# pmu.net
KiCad netlist of a schematic drawn in Altium Designer
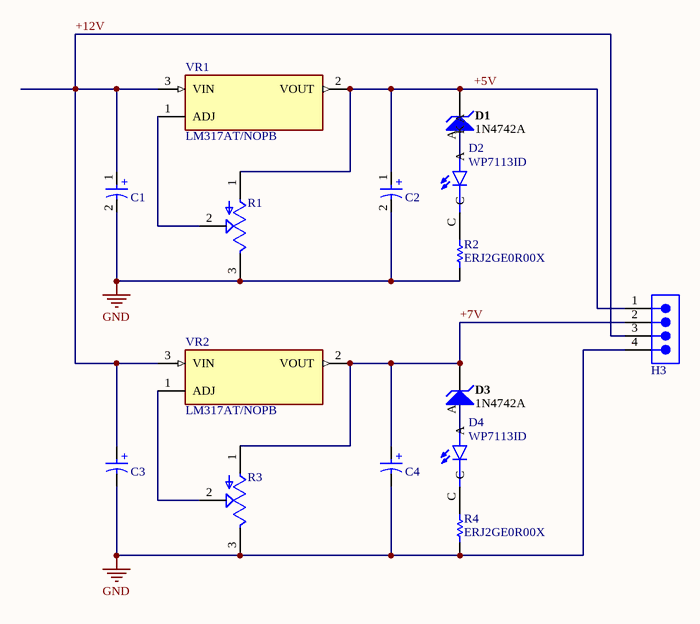
[diagram p0: pmu.SchDoc]

(export (version "E")
  (design (tool "Eeschema 10.0.6"))
  (components
    (comp (ref "C1")
      (value "2.2µF")
      (footprint "pmu:WCAP-ATG5_D5H11")
      (description "WCAP-ATG5 Aluminum Electrolytic Capacitor, Radial, THT, D5 x H11mm, 2.2µF, 50V")
      (fields
        (field (name "MANUFACTURER PART NUMBER") "860020672006")
        (field (name "MANUFACTURER") "Wurth Elektronik")
      )
      (libsource (lib "1ufcap-Altium_WCAP-ATG5_rev22d") (part "860020672006"))
    )
    (comp (ref "C2")
      (value "1.1uF")
      (footprint "pmu:WCAP-ATG5_D5H11")
      (description "WCAP-ATG5 Aluminum Electrolytic Capacitor, Radial, THT, D5 x H11mm, 2.2µF, 50V")
      (fields
        (field (name "MANUFACTURER PART NUMBER") "860020672006")
        (field (name "MANUFACTURER") "Wurth Elektronik")
      )
      (libsource (lib "1ufcap-Altium_WCAP-ATG5_rev22d") (part "860020672006"))
    )
    (comp (ref "C3")
      (value "2.2µF")
      (footprint "pmu:WCAP-ATG5_D5H11")
      (description "WCAP-ATG5 Aluminum Electrolytic Capacitor, Radial, THT, D5 x H11mm, 2.2µF, 50V")
      (fields
        (field (name "MANUFACTURER PART NUMBER") "860020672006")
        (field (name "MANUFACTURER") "Wurth Elektronik")
      )
      (libsource (lib "") (part "860020672006_1"))
    )
    (comp (ref "C4")
      (value "1.1uF")
      (footprint "pmu:WCAP-ATG5_D5H11")
      (description "WCAP-ATG5 Aluminum Electrolytic Capacitor, Radial, THT, D5 x H11mm, 2.2µF, 50V")
      (fields
        (field (name "MANUFACTURER PART NUMBER") "860020672006")
        (field (name "MANUFACTURER") "Wurth Elektronik")
      )
      (libsource (lib "") (part "860020672006_1"))
    )
    (comp (ref "D1")
      (value "1N4742A")
      (footprint "FAIR-DO-41-2_V")
      (description "Zener Diode, 12V, 1W, 5%, -65 to 200 degC, 2-Pin DO-41, Body 2.72 x 5.2 mm, RoHS")
      (fields (field (name "TOLERANCE") "5%") (field (name "MANUFACTURER") "Fairchild Semiconductor"))
      (libsource (lib "Altium Content Vault") (part "FAIR-DZEN-A1K2-2"))
    )
    (comp (ref "D2")
      (value "WP7113ID")
      (footprint "pmu:LED_WP7113ID")
      (description "Red 617nm LED Indication - Discrete 2V Radial")
      (fields (field (name "MF") "Kingbright"))
      (libsource (lib "leds-WP7113ID") (part "WP7113ID"))
    )
    (comp (ref "D3")
      (value "1N4742A")
      (footprint "FAIR-DO-41-2_V")
      (description "Zener Diode, 12V, 1W, 5%, -65 to 200 degC, 2-Pin DO-41, Body 2.72 x 5.2 mm, RoHS")
      (fields (field (name "TOLERANCE") "5%") (field (name "MANUFACTURER") "Fairchild Semiconductor"))
      (libsource (lib "") (part "FAIR-DZEN-A1K2-2_1"))
    )
    (comp (ref "D4")
      (value "WP7113ID")
      (footprint "pmu:LED_WP7113ID")
      (description "Red 617nm LED Indication - Discrete 2V Radial")
      (fields (field (name "MF") "Kingbright"))
      (libsource (lib "leds-WP7113ID") (part "WP7113ID"))
    )
    (comp (ref "H3")
      (value "61300411121")
      (footprint "61300411121")
      (description "WR-PHD Pin Header, THT, Vertical, pitch 2.54mm, 1 Row, 4P")
      (fields (field (name "MANUFACTURER") "Wurth Elektronik"))
      (libsource (lib "pmu") (part "61300411121"))
    )
    (comp (ref "R1")
      (value "~")
      (footprint "TRIM_3362P-1-103LF")
      (description "10 kOhms 0.5W, 1/2W PC Pins Through Hole Trimmer Potentiometer Cermet 1 Turn Top Adjustment")
      (fields (field (name "DIGI-KEY_PART_NUMBER") "3362P-103LF-ND") (field (name "MF") "Bourns"))
      (libsource (lib "*") (part "3362P-1-103LF"))
    )
    (comp (ref "R2")
      (value "ERJ2GE0R00X")
      (footprint "RESC1005X40X25LL05T05")
      (description "Chip Resistor, 0 Ohm, 0.1 W, -55 to 155 degC, 0402 (1005 Metric), RoHS, Tape and Reel")
      (fields (field (name "MANUFACTURER") "Panasonic") (field (name "TOLERANCE") "5%"))
      (libsource (lib "Altium Content Vault") (part "RES-2"))
    )
    (comp (ref "R3")
      (value "~")
      (footprint "TRIM_3362P-1-103LF")
      (description "10 kOhms 0.5W, 1/2W PC Pins Through Hole Trimmer Potentiometer Cermet 1 Turn Top Adjustment")
      (fields (field (name "DIGI-KEY_PART_NUMBER") "3362P-103LF-ND") (field (name "MF") "Bourns"))
      (libsource (lib "*") (part "3362P-1-103LF"))
    )
    (comp (ref "R4")
      (value "ERJ2GE0R00X")
      (footprint "RESC1005X40X25LL05T05")
      (description "Chip Resistor, 0 Ohm, 0.1 W, -55 to 155 degC, 0402 (1005 Metric), RoHS, Tape and Reel")
      (fields (field (name "MANUFACTURER") "Panasonic") (field (name "TOLERANCE") "5%"))
      (libsource (lib "Altium Content Vault") (part "RES-2"))
    )
    (comp (ref "VR1")
      (value "LM317AT/NOPB")
      (footprint "pmu:TO254P1054X470X1955-3")
      (libsource (lib "vreg-LM317AT_NOPB") (part "LM317AT/NOPB"))
    )
    (comp (ref "VR2")
      (value "LM317AT/NOPB")
      (footprint "pmu:TO254P1054X470X1955-3")
      (libsource (lib "vreg-LM317AT_NOPB") (part "LM317AT/NOPB"))
    )
  )
  (nets
    (net (code "1") (name "/+5V") (class "Default")
      (node (ref "C2") (pin "1") (pinfunction "P_1") (pintype "passive"))
      (node (ref "D1") (pin "2") (pinfunction "K_2") (pintype "passive"))
      (node (ref "H3") (pin "1") (pinfunction "1_1") (pintype "passive"))
      (node (ref "R1") (pin "1") (pinfunction "CCW_1") (pintype "passive"))
      (node (ref "VR1") (pin "2") (pinfunction "VOUT_2") (pintype "output"))
    )
    (net (code "2") (name "/+7V") (class "Default")
      (node (ref "C4") (pin "1") (pinfunction "P_1") (pintype "passive"))
      (node (ref "D3") (pin "2") (pinfunction "K_2") (pintype "passive"))
      (node (ref "H3") (pin "2") (pinfunction "2_2") (pintype "passive"))
      (node (ref "R3") (pin "1") (pinfunction "CCW_1") (pintype "passive"))
      (node (ref "VR2") (pin "2") (pinfunction "VOUT_2") (pintype "output"))
    )
    (net (code "3") (name "/+12V") (class "Default")
      (node (ref "C1") (pin "1") (pinfunction "P_1") (pintype "passive"))
      (node (ref "C3") (pin "1") (pinfunction "P_1") (pintype "passive"))
      (node (ref "H3") (pin "3") (pinfunction "3_3") (pintype "passive"))
      (node (ref "VR1") (pin "3") (pinfunction "VIN_3") (pintype "input"))
      (node (ref "VR2") (pin "3") (pinfunction "VIN_3") (pintype "input"))
    )
    (net (code "4") (name "GND") (class "Default")
      (node (ref "C1") (pin "2") (pinfunction "N_2") (pintype "passive"))
      (node (ref "C2") (pin "2") (pinfunction "N_2") (pintype "passive"))
      (node (ref "C3") (pin "2") (pinfunction "N_2") (pintype "passive"))
      (node (ref "C4") (pin "2") (pinfunction "N_2") (pintype "passive"))
      (node (ref "H3") (pin "4") (pinfunction "4_4") (pintype "passive"))
      (node (ref "R1") (pin "3") (pinfunction "CW_3") (pintype "passive"))
      (node (ref "R2") (pin "1") (pinfunction "1_1") (pintype "passive"))
      (node (ref "R3") (pin "3") (pinfunction "CW_3") (pintype "passive"))
      (node (ref "R4") (pin "1") (pinfunction "1_1") (pintype "passive"))
    )
    (net (code "5") (name "Net-(D1-A)") (class "Default")
      (node (ref "D1") (pin "1") (pinfunction "A_1") (pintype "passive"))
      (node (ref "D2") (pin "A") (pinfunction "A_A") (pintype "passive"))
    )
    (net (code "6") (name "Net-(D2-PadC)") (class "Default")
      (node (ref "D2") (pin "C") (pinfunction "C_C") (pintype "passive"))
      (node (ref "R2") (pin "2") (pinfunction "2_2") (pintype "passive"))
    )
    (net (code "7") (name "Net-(D3-A)") (class "Default")
      (node (ref "D3") (pin "1") (pinfunction "A_1") (pintype "passive"))
      (node (ref "D4") (pin "A") (pinfunction "A_A") (pintype "passive"))
    )
    (net (code "8") (name "Net-(D4-PadC)") (class "Default")
      (node (ref "D4") (pin "C") (pinfunction "C_C") (pintype "passive"))
      (node (ref "R4") (pin "2") (pinfunction "2_2") (pintype "passive"))
    )
    (net (code "9") (name "Net-(R1-WIPER)") (class "Default")
      (node (ref "R1") (pin "2") (pinfunction "WIPER_2") (pintype "passive"))
      (node (ref "VR1") (pin "1") (pinfunction "ADJ_1") (pintype "passive"))
    )
    (net (code "10") (name "Net-(R3-WIPER)") (class "Default")
      (node (ref "R3") (pin "2") (pinfunction "WIPER_2") (pintype "passive"))
      (node (ref "VR2") (pin "1") (pinfunction "ADJ_1") (pintype "passive"))
    )
  )
)
